# ESP32ProtypeBoard.net
KiCad netlist of a schematic drawn in EAGLE
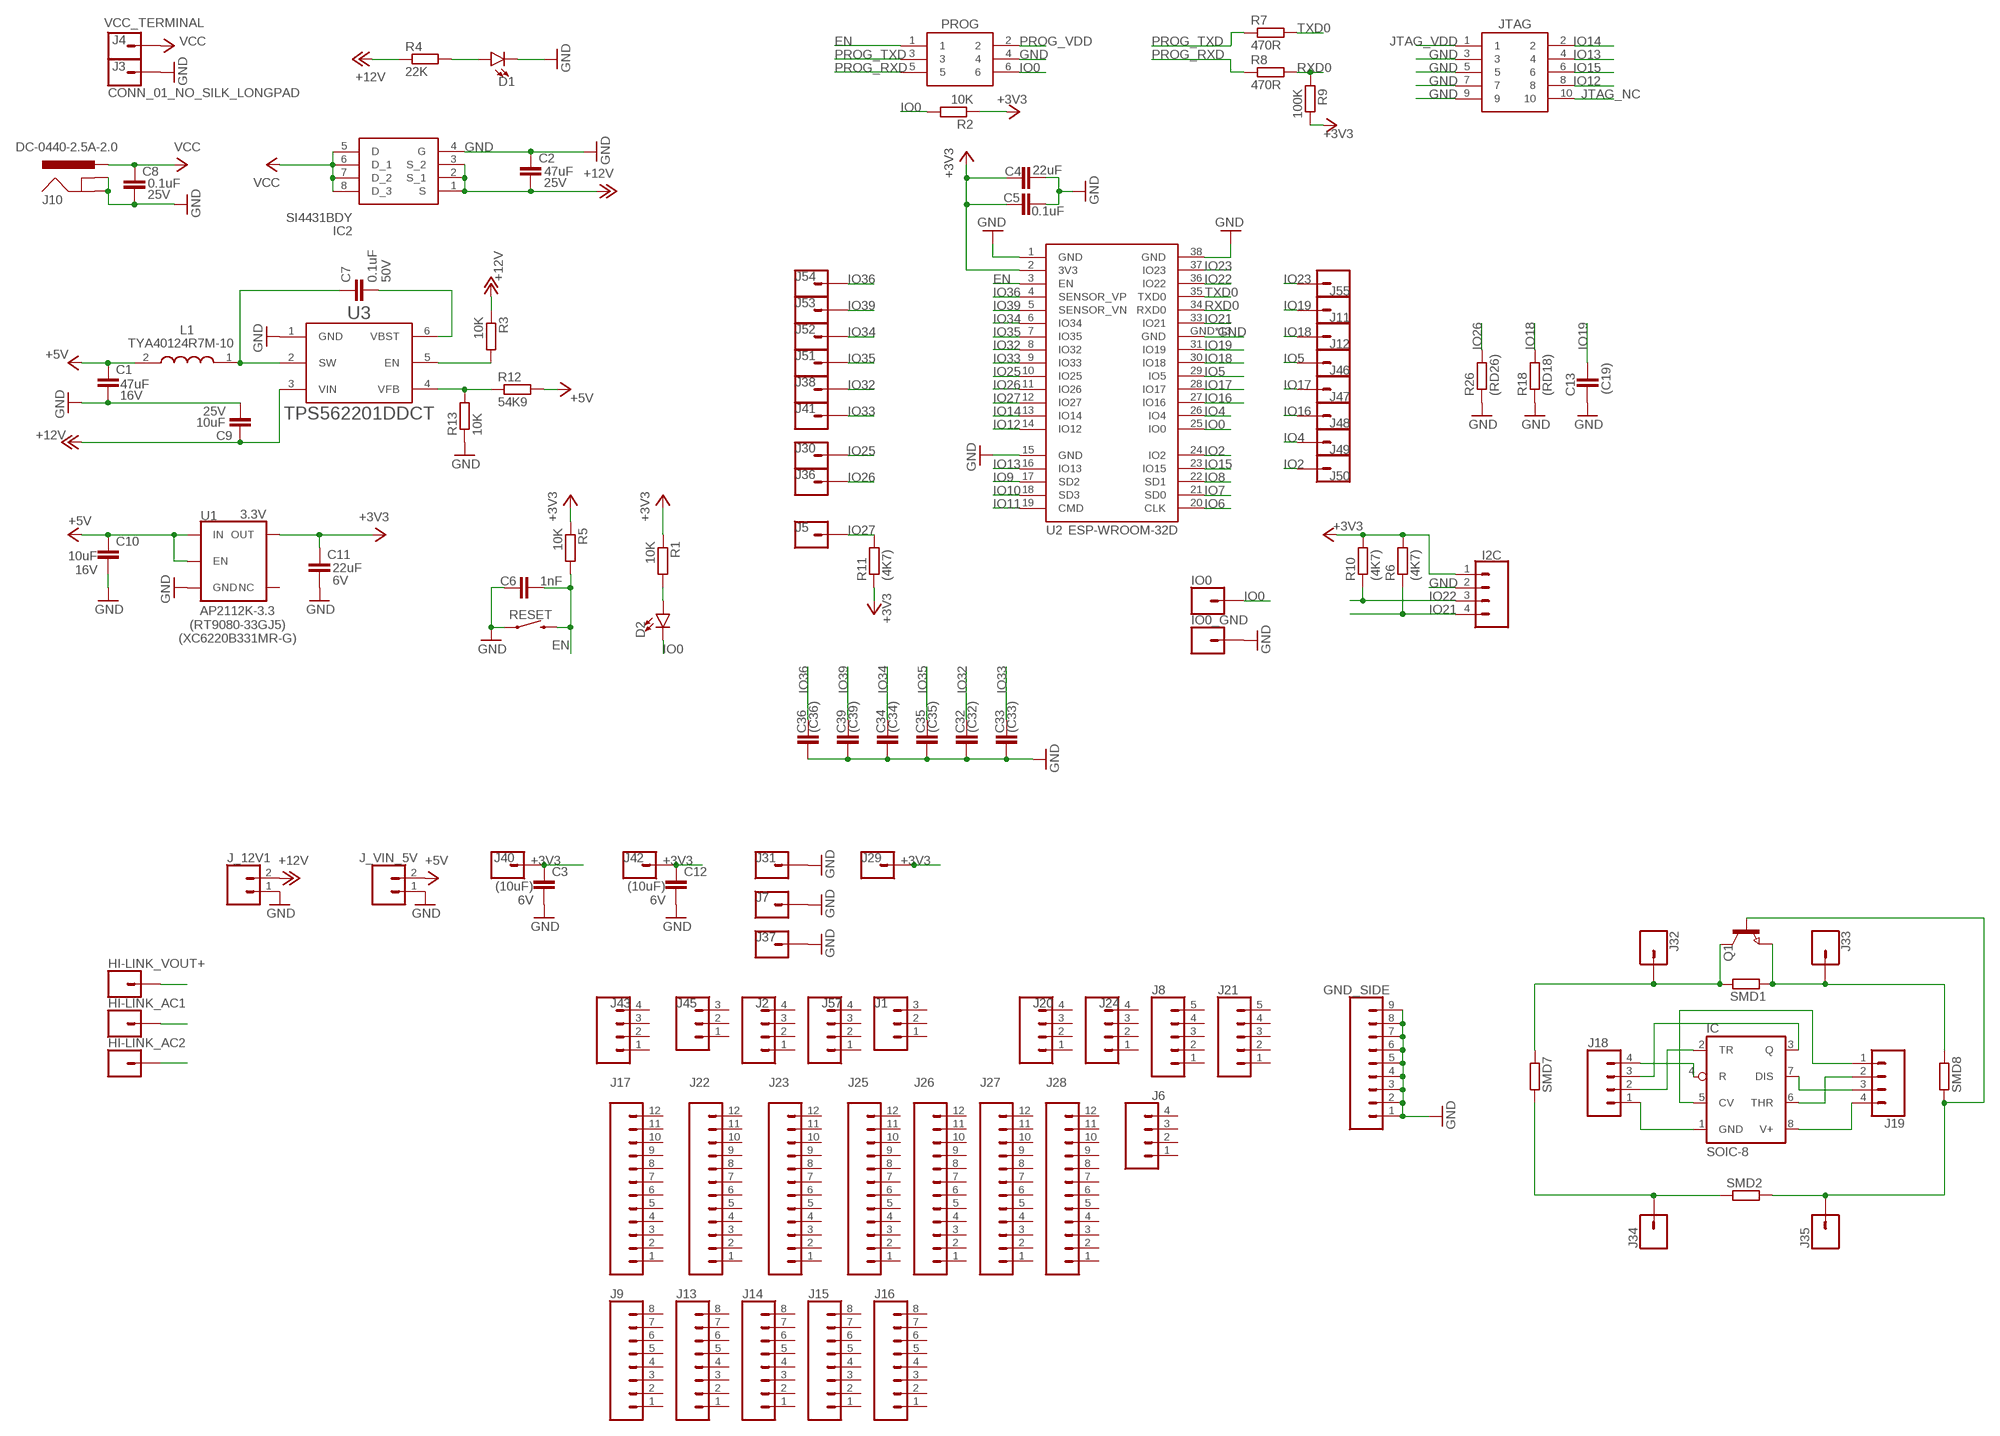
[diagram p0: schematic, sheet 1]

(export (version "E")
  (design (tool "Eeschema 10.0.6"))
  (components
    (comp (ref "C1")
      (value "47uF")
      (footprint "eagle-import:C1206K")
      (fields (field (name "VOLTAGE") "16V"))
      (libsource (lib "eagle-import") (part "C-EUC1206K"))
    )
    (comp (ref "C2")
      (value "47uF")
      (footprint "eagle-import:C1206K")
      (fields (field (name "VOLTAGE") "25V"))
      (libsource (lib "eagle-import") (part "C-EUC1206K"))
    )
    (comp (ref "C3")
      (value "(10uF)")
      (footprint "eagle-import:C0805K")
      (fields (field (name "VOLTAGE") "6V"))
      (libsource (lib "eagle-import") (part "C-EUC0805K"))
    )
    (comp (ref "C4")
      (value "22uF")
      (footprint "eagle-import:C0805K")
      (libsource (lib "eagle-import") (part "C-EUC0805K"))
    )
    (comp (ref "C5")
      (value "0.1uF")
      (footprint "eagle-import:C0805K")
      (libsource (lib "eagle-import") (part "C-EUC0805K"))
    )
    (comp (ref "C6")
      (value "1nF")
      (footprint "eagle-import:C0805K")
      (libsource (lib "eagle-import") (part "C-EUC0805K"))
    )
    (comp (ref "C7")
      (value "0.1uF")
      (footprint "eagle-import:C0805K")
      (fields (field (name "VOLTAGE") "50V"))
      (libsource (lib "eagle-import") (part "C-EUC0805K"))
    )
    (comp (ref "C8")
      (value "0.1uF")
      (footprint "eagle-import:C0805K")
      (fields (field (name "VOLTAGE") "25V"))
      (libsource (lib "eagle-import") (part "C-EUC0805K"))
    )
    (comp (ref "C9")
      (value "10uF")
      (footprint "eagle-import:C0805K")
      (fields (field (name "VOLTAGE") "25V"))
      (libsource (lib "eagle-import") (part "C-EUC0805K"))
    )
    (comp (ref "C10")
      (value "10uF")
      (footprint "eagle-import:C0805K")
      (fields (field (name "VOLTAGE") "16V"))
      (libsource (lib "eagle-import") (part "C-EUC0805K"))
    )
    (comp (ref "C11")
      (value "22uF")
      (footprint "eagle-import:C0805K")
      (fields (field (name "VOLTAGE") "6V"))
      (libsource (lib "eagle-import") (part "C-EUC0805K"))
    )
    (comp (ref "C12")
      (value "(10uF)")
      (footprint "eagle-import:C0805K")
      (fields (field (name "VOLTAGE") "6V"))
      (libsource (lib "eagle-import") (part "C-EUC0805K"))
    )
    (comp (ref "C13")
      (value "(C19)")
      (footprint "eagle-import:C0805K")
      (libsource (lib "eagle-import") (part "C-EUC0805K"))
    )
    (comp (ref "C32")
      (value "(C32)")
      (footprint "eagle-import:C0805K")
      (libsource (lib "eagle-import") (part "C-EUC0805K"))
    )
    (comp (ref "C33")
      (value "(C33)")
      (footprint "eagle-import:C0805K")
      (libsource (lib "eagle-import") (part "C-EUC0805K"))
    )
    (comp (ref "C34")
      (value "(C34)")
      (footprint "eagle-import:C0805K")
      (libsource (lib "eagle-import") (part "C-EUC0805K"))
    )
    (comp (ref "C35")
      (value "(C35)")
      (footprint "eagle-import:C0805K")
      (libsource (lib "eagle-import") (part "C-EUC0805K"))
    )
    (comp (ref "C36")
      (value "(C36)")
      (footprint "eagle-import:C0805K")
      (libsource (lib "eagle-import") (part "C-EUC0805K"))
    )
    (comp (ref "C39")
      (value "(C39)")
      (footprint "eagle-import:C0805K")
      (libsource (lib "eagle-import") (part "C-EUC0805K"))
    )
    (comp (ref "D1")
      (value "PWR")
      (footprint "eagle-import:CHIPLED_0805")
      (libsource (lib "eagle-import") (part "LEDCHIPLED_0805"))
    )
    (comp (ref "D2")
      (value "GREEN")
      (footprint "eagle-import:CHIPLED_0805")
      (libsource (lib "eagle-import") (part "LEDCHIPLED_0805"))
    )
    (comp (ref "GND_SIDE")
      (value "CONN_09NO_SILK")
      (footprint "eagle-import:1X09_NO_SILK")
      (libsource (lib "eagle-import") (part "CONN_09NO_SILK"))
    )
    (comp (ref "HI-LINK_AC1")
      (value "CONN_01PTH_NO_SILK_KIT")
      (footprint "eagle-import:1X01NS_KIT")
      (libsource (lib "eagle-import") (part "SparkFun-Connectors_513_CONN_01PTH_NO_SILK_KIT"))
    )
    (comp (ref "HI-LINK_AC2")
      (value "CONN_01PTH_NO_SILK_KIT")
      (footprint "eagle-import:1X01NS_KIT")
      (libsource (lib "eagle-import") (part "SparkFun-Connectors_513_CONN_01PTH_NO_SILK_KIT"))
    )
    (comp (ref "HI-LINK_VOUT+")
      (value "CONN_01PTH_NO_SILK_KIT")
      (footprint "eagle-import:1X01NS_KIT")
      (libsource (lib "eagle-import") (part "SparkFun-Connectors_513_CONN_01PTH_NO_SILK_KIT"))
    )
    (comp (ref "I2C")
      (value "CONN_041X04_NO_SILK")
      (footprint "eagle-import:1X04_NO_SILK")
      (libsource (lib "eagle-import") (part "SparkFun-Connectors_513_CONN_041X04_NO_SILK"))
    )
    (comp (ref "IC")
      (value "SOIC-8")
      (footprint "eagle-import:SO08")
      (libsource (lib "eagle-import") (part "555DLM"))
    )
    (comp (ref "IC2")
      (value "SI4431BDY")
      (footprint "eagle-import:SOIC127P600X175-8N")
      (fields (field (name "ARROW_PART_NUMBER") "SI4431BDY-T1-E3") (field (name "RS_PART_NUMBER") "7104714P"))
      (libsource (lib "eagle-import") (part "SI4431BDY-T1-E3"))
    )
    (comp (ref "IO0")
      (value "CONN_01PTH_NO_SILK_KIT")
      (footprint "eagle-import:1X01NS_KIT")
      (libsource (lib "eagle-import") (part "SparkFun-Connectors_513_CONN_01PTH_NO_SILK_KIT"))
    )
    (comp (ref "IO0_GND")
      (value "CONN_01PTH_NO_SILK_YES_STOP")
      (footprint "eagle-import:1X01_NO_SILK")
      (libsource (lib "eagle-import") (part "SparkFun-Connectors_513_CONN_01PTH_NO_SILK_YES_STOP"))
    )
    (comp (ref "J1")
      (value "CONN_03_NO_SILK")
      (footprint "eagle-import:1X03_NO_SILK")
      (libsource (lib "eagle-import") (part "CONN_03_NO_SILK"))
    )
    (comp (ref "J2")
      (value "CONN_04_NO_SILK")
      (footprint "eagle-import:1X04_NO_SILK")
      (libsource (lib "eagle-import") (part "CONN_04_NO_SILK"))
    )
    (comp (ref "J3")
      (value "CONN_01_NO_SILK_LONGPAD")
      (footprint "eagle-import:1X01_NO_SILK_LONGPAD")
      (libsource (lib "eagle-import") (part "CONN_01_NO_SILK_LONGPAD"))
    )
    (comp (ref "J4")
      (value "VCC_TERMINAL")
      (footprint "eagle-import:1X01_NO_SILK_LONGPAD")
      (libsource (lib "eagle-import") (part "CONN_01_NO_SILK_LONGPAD"))
    )
    (comp (ref "J5")
      (value "CONN_01_NO_SILK")
      (footprint "eagle-import:1X01_NO_SILK")
      (libsource (lib "eagle-import") (part "CONN_01_NO_SILK"))
    )
    (comp (ref "J6")
      (value "CONN_04_NO_SILK")
      (footprint "eagle-import:1X04_NO_SILK")
      (libsource (lib "eagle-import") (part "CONN_04_NO_SILK"))
    )
    (comp (ref "J7")
      (value "CONN_01_NO_SILK")
      (footprint "eagle-import:1X01_NO_SILK")
      (libsource (lib "eagle-import") (part "CONN_01_NO_SILK"))
    )
    (comp (ref "J8")
      (value "CONN_05_NO_SILK")
      (footprint "eagle-import:1X05_NO_SILK")
      (libsource (lib "eagle-import") (part "CONN_05_NO_SILK"))
    )
    (comp (ref "J9")
      (value "CONN_08NO_SILK_FEMALE_PTH")
      (footprint "eagle-import:1X08_NO_SILK")
      (libsource (lib "eagle-import") (part "CONN_08NO_SILK_FEMALE_PTH"))
    )
    (comp (ref "J10")
      (value "DC-0440-2.5A-2.0")
      (footprint "eagle-import:DC044025A20")
      (libsource (lib "eagle-import") (part "DC-0440-2.5A-2.0"))
    )
    (comp (ref "J11")
      (value "CONN_01PTH_NO_SILK_YES_STOP")
      (footprint "eagle-import:1X01_NO_SILK")
      (libsource (lib "eagle-import") (part "SparkFun-Connectors_513_CONN_01PTH_NO_SILK_YES_STOP"))
    )
    (comp (ref "J12")
      (value "CONN_01PTH_NO_SILK_YES_STOP")
      (footprint "eagle-import:1X01_NO_SILK")
      (libsource (lib "eagle-import") (part "SparkFun-Connectors_513_CONN_01PTH_NO_SILK_YES_STOP"))
    )
    (comp (ref "J13")
      (value "CONN_08NO_SILK_FEMALE_PTH")
      (footprint "eagle-import:1X08_NO_SILK")
      (libsource (lib "eagle-import") (part "CONN_08NO_SILK_FEMALE_PTH"))
    )
    (comp (ref "J14")
      (value "CONN_08NO_SILK_FEMALE_PTH")
      (footprint "eagle-import:1X08_NO_SILK")
      (libsource (lib "eagle-import") (part "CONN_08NO_SILK_FEMALE_PTH"))
    )
    (comp (ref "J15")
      (value "CONN_08NO_SILK_FEMALE_PTH")
      (footprint "eagle-import:1X08_NO_SILK")
      (libsource (lib "eagle-import") (part "CONN_08NO_SILK_FEMALE_PTH"))
    )
    (comp (ref "J16")
      (value "CONN_08NO_SILK_FEMALE_PTH")
      (footprint "eagle-import:1X08_NO_SILK")
      (libsource (lib "eagle-import") (part "CONN_08NO_SILK_FEMALE_PTH"))
    )
    (comp (ref "J17")
      (value "CONN_12NO_SILK")
      (footprint "eagle-import:1X12_NO_SILK")
      (libsource (lib "eagle-import") (part "CONN_12NO_SILK"))
    )
    (comp (ref "J18")
      (value "CONN_041X04_NO_SILK")
      (footprint "eagle-import:1X04_NO_SILK")
      (libsource (lib "eagle-import") (part "CONN_041X04_NO_SILK"))
    )
    (comp (ref "J19")
      (value "CONN_041X04_NO_SILK")
      (footprint "eagle-import:1X04_NO_SILK")
      (libsource (lib "eagle-import") (part "CONN_041X04_NO_SILK"))
    )
    (comp (ref "J20")
      (value "CONN_04_NO_SILK")
      (footprint "eagle-import:1X04_NO_SILK")
      (libsource (lib "eagle-import") (part "CONN_04_NO_SILK"))
    )
    (comp (ref "J21")
      (value "CONN_05_NO_SILK")
      (footprint "eagle-import:1X05_NO_SILK")
      (libsource (lib "eagle-import") (part "CONN_05_NO_SILK"))
    )
    (comp (ref "J22")
      (value "CONN_12NO_SILK")
      (footprint "eagle-import:1X12_NO_SILK")
      (libsource (lib "eagle-import") (part "CONN_12NO_SILK"))
    )
    (comp (ref "J23")
      (value "CONN_12NO_SILK")
      (footprint "eagle-import:1X12_NO_SILK")
      (libsource (lib "eagle-import") (part "CONN_12NO_SILK"))
    )
    (comp (ref "J24")
      (value "CONN_04_NO_SILK")
      (footprint "eagle-import:1X04_NO_SILK")
      (libsource (lib "eagle-import") (part "CONN_04_NO_SILK"))
    )
    (comp (ref "J25")
      (value "CONN_12NO_SILK")
      (footprint "eagle-import:1X12_NO_SILK")
      (libsource (lib "eagle-import") (part "CONN_12NO_SILK"))
    )
    (comp (ref "J26")
      (value "CONN_12NO_SILK")
      (footprint "eagle-import:1X12_NO_SILK")
      (libsource (lib "eagle-import") (part "CONN_12NO_SILK"))
    )
    (comp (ref "J27")
      (value "CONN_12NO_SILK")
      (footprint "eagle-import:1X12_NO_SILK")
      (libsource (lib "eagle-import") (part "CONN_12NO_SILK"))
    )
    (comp (ref "J28")
      (value "CONN_12NO_SILK")
      (footprint "eagle-import:1X12_NO_SILK")
      (libsource (lib "eagle-import") (part "CONN_12NO_SILK"))
    )
    (comp (ref "J29")
      (value "CONN_01_NO_SILK")
      (footprint "eagle-import:1X01_NO_SILK")
      (libsource (lib "eagle-import") (part "CONN_01_NO_SILK"))
    )
    (comp (ref "J30")
      (value "CONN_01_NO_SILK")
      (footprint "eagle-import:1X01_NO_SILK")
      (libsource (lib "eagle-import") (part "CONN_01_NO_SILK"))
    )
    (comp (ref "J31")
      (value "CONN_01_NO_SILK")
      (footprint "eagle-import:1X01_NO_SILK")
      (libsource (lib "eagle-import") (part "CONN_01_NO_SILK"))
    )
    (comp (ref "J32")
      (value "CONN_01PTH_NO_SILK_YES_STOP")
      (footprint "eagle-import:1X01_NO_SILK")
      (libsource (lib "eagle-import") (part "CONN_01PTH_NO_SILK_YES_STOP"))
    )
    (comp (ref "J33")
      (value "CONN_01PTH_NO_SILK_YES_STOP")
      (footprint "eagle-import:1X01_NO_SILK")
      (libsource (lib "eagle-import") (part "CONN_01PTH_NO_SILK_YES_STOP"))
    )
    (comp (ref "J34")
      (value "CONN_01PTH_NO_SILK_YES_STOP")
      (footprint "eagle-import:1X01_NO_SILK")
      (libsource (lib "eagle-import") (part "CONN_01PTH_NO_SILK_YES_STOP"))
    )
    (comp (ref "J35")
      (value "CONN_01PTH_NO_SILK_YES_STOP")
      (footprint "eagle-import:1X01_NO_SILK")
      (libsource (lib "eagle-import") (part "CONN_01PTH_NO_SILK_YES_STOP"))
    )
    (comp (ref "J36")
      (value "CONN_01_NO_SILK")
      (footprint "eagle-import:1X01_NO_SILK")
      (libsource (lib "eagle-import") (part "CONN_01_NO_SILK"))
    )
    (comp (ref "J37")
      (value "CONN_01_NO_SILK")
      (footprint "eagle-import:1X01_NO_SILK")
      (libsource (lib "eagle-import") (part "CONN_01_NO_SILK"))
    )
    (comp (ref "J38")
      (value "CONN_01_NO_SILK")
      (footprint "eagle-import:1X01_NO_SILK")
      (libsource (lib "eagle-import") (part "CONN_01_NO_SILK"))
    )
    (comp (ref "J40")
      (value "CONN_01_NO_SILK")
      (footprint "eagle-import:1X01_NO_SILK")
      (libsource (lib "eagle-import") (part "CONN_01_NO_SILK"))
    )
    (comp (ref "J41")
      (value "CONN_01_NO_SILK")
      (footprint "eagle-import:1X01_NO_SILK")
      (libsource (lib "eagle-import") (part "CONN_01_NO_SILK"))
    )
    (comp (ref "J42")
      (value "CONN_01_NO_SILK")
      (footprint "eagle-import:1X01_NO_SILK")
      (libsource (lib "eagle-import") (part "CONN_01_NO_SILK"))
    )
    (comp (ref "J43")
      (value "CONN_04_NO_SILK")
      (footprint "eagle-import:1X04_NO_SILK")
      (libsource (lib "eagle-import") (part "CONN_04_NO_SILK"))
    )
    (comp (ref "J45")
      (value "CONN_03_NO_SILK")
      (footprint "eagle-import:1X03_NO_SILK")
      (libsource (lib "eagle-import") (part "CONN_03_NO_SILK"))
    )
    (comp (ref "J46")
      (value "CONN_01PTH_NO_SILK_YES_STOP")
      (footprint "eagle-import:1X01_NO_SILK")
      (libsource (lib "eagle-import") (part "SparkFun-Connectors_513_CONN_01PTH_NO_SILK_YES_STOP"))
    )
    (comp (ref "J47")
      (value "CONN_01PTH_NO_SILK_YES_STOP")
      (footprint "eagle-import:1X01_NO_SILK")
      (libsource (lib "eagle-import") (part "SparkFun-Connectors_513_CONN_01PTH_NO_SILK_YES_STOP"))
    )
    (comp (ref "J48")
      (value "CONN_01PTH_NO_SILK_YES_STOP")
      (footprint "eagle-import:1X01_NO_SILK")
      (libsource (lib "eagle-import") (part "SparkFun-Connectors_513_CONN_01PTH_NO_SILK_YES_STOP"))
    )
    (comp (ref "J49")
      (value "CONN_01PTH_NO_SILK_YES_STOP")
      (footprint "eagle-import:1X01_NO_SILK")
      (libsource (lib "eagle-import") (part "SparkFun-Connectors_513_CONN_01PTH_NO_SILK_YES_STOP"))
    )
    (comp (ref "J50")
      (value "CONN_01PTH_NO_SILK_YES_STOP")
      (footprint "eagle-import:1X01_NO_SILK")
      (libsource (lib "eagle-import") (part "SparkFun-Connectors_513_CONN_01PTH_NO_SILK_YES_STOP"))
    )
    (comp (ref "J51")
      (value "CONN_01_NO_SILK")
      (footprint "eagle-import:1X01_NO_SILK")
      (libsource (lib "eagle-import") (part "CONN_01_NO_SILK"))
    )
    (comp (ref "J52")
      (value "CONN_01_NO_SILK")
      (footprint "eagle-import:1X01_NO_SILK")
      (libsource (lib "eagle-import") (part "CONN_01_NO_SILK"))
    )
    (comp (ref "J53")
      (value "CONN_01_NO_SILK")
      (footprint "eagle-import:1X01_NO_SILK")
      (libsource (lib "eagle-import") (part "CONN_01_NO_SILK"))
    )
    (comp (ref "J54")
      (value "CONN_01_NO_SILK")
      (footprint "eagle-import:1X01_NO_SILK")
      (libsource (lib "eagle-import") (part "CONN_01_NO_SILK"))
    )
    (comp (ref "J55")
      (value "CONN_01PTH_NO_SILK_YES_STOP")
      (footprint "eagle-import:1X01_NO_SILK")
      (libsource (lib "eagle-import") (part "SparkFun-Connectors_513_CONN_01PTH_NO_SILK_YES_STOP"))
    )
    (comp (ref "J57")
      (value "CONN_04_NO_SILK")
      (footprint "eagle-import:1X04_NO_SILK")
      (libsource (lib "eagle-import") (part "CONN_04_NO_SILK"))
    )
    (comp (ref "JTAG")
      (value "DC3-10-1P27")
      (footprint "eagle-import:DC3-10-1P27")
      (fields (field (name "ARROW_PART_NUMBER") "3220-10-0100-00"))
      (libsource (lib "eagle-import") (part "DC3-10-1P27"))
    )
    (comp (ref "J_12V1")
      (value "CONN_021X02_NO_SILK")
      (footprint "eagle-import:1X02_NO_SILK")
      (libsource (lib "eagle-import") (part "CONN_021X02_NO_SILK"))
    )
    (comp (ref "J_VIN_5V")
      (value "CONN_021X02_NO_SILK")
      (footprint "eagle-import:1X02_NO_SILK")
      (libsource (lib "eagle-import") (part "CONN_021X02_NO_SILK"))
    )
    (comp (ref "L1")
      (value "TYA40124R7M-10")
      (footprint "eagle-import:INDPM4040X130N")
      (libsource (lib "eagle-import") (part "TYA40124R7M-10"))
    )
    (comp (ref "PROG")
      (value "DC3-06-1P27")
      (footprint "eagle-import:DC3-06-1P27")
      (libsource (lib "eagle-import") (part "DC3-06-1P27"))
    )
    (comp (ref "Q1")
      (value "NPN-TRANSISTOR_SOT23")
      (footprint "eagle-import:SOT23")
      (libsource (lib "eagle-import") (part "NPN-TRANSISTOR_SOT23"))
    )
    (comp (ref "R1")
      (value "10K")
      (footprint "eagle-import:R0805")
      (libsource (lib "eagle-import") (part "R-EU_R0805"))
    )
    (comp (ref "R2")
      (value "10K")
      (footprint "eagle-import:R0805")
      (libsource (lib "eagle-import") (part "R-EU_R0805"))
    )
    (comp (ref "R3")
      (value "10K")
      (footprint "eagle-import:R0805")
      (libsource (lib "eagle-import") (part "R-EU_R0805"))
    )
    (comp (ref "R4")
      (value "22K")
      (footprint "eagle-import:R0805")
      (libsource (lib "eagle-import") (part "R-EU_R0805"))
    )
    (comp (ref "R5")
      (value "10K")
      (footprint "eagle-import:R0805")
      (libsource (lib "eagle-import") (part "R-EU_R0805"))
    )
    (comp (ref "R6")
      (value "(4K7)")
      (footprint "eagle-import:R0805")
      (libsource (lib "eagle-import") (part "R-EU_R0805"))
    )
    (comp (ref "R7")
      (value "470R")
      (footprint "eagle-import:R0805")
      (libsource (lib "eagle-import") (part "R-EU_R0805"))
    )
    (comp (ref "R8")
      (value "470R")
      (footprint "eagle-import:R0805")
      (libsource (lib "eagle-import") (part "R-EU_R0805"))
    )
    (comp (ref "R9")
      (value "100K")
      (footprint "eagle-import:R0805")
      (libsource (lib "eagle-import") (part "R-EU_R0805"))
    )
    (comp (ref "R10")
      (value "(4K7)")
      (footprint "eagle-import:R0805")
      (libsource (lib "eagle-import") (part "R-EU_R0805"))
    )
    (comp (ref "R11")
      (value "(4K7)")
      (footprint "eagle-import:R0805")
      (libsource (lib "eagle-import") (part "R-EU_R0805"))
    )
    (comp (ref "R12")
      (value "54K9")
      (footprint "eagle-import:R0805")
      (libsource (lib "eagle-import") (part "R-EU_R0805"))
    )
    (comp (ref "R13")
      (value "10K")
      (footprint "eagle-import:R0805")
      (libsource (lib "eagle-import") (part "R-EU_R0805"))
    )
    (comp (ref "R18")
      (value "(RD18)")
      (footprint "eagle-import:R0805")
      (libsource (lib "eagle-import") (part "R-EU_R0805"))
    )
    (comp (ref "R26")
      (value "(RD26)")
      (footprint "eagle-import:R0805")
      (libsource (lib "eagle-import") (part "R-EU_R0805"))
    )
    (comp (ref "RESET")
      (value "RESET")
      (footprint "eagle-import:TACTILE_SWITCH_SMD_4X3MM")
      (libsource (lib "eagle-import") (part "TACTILE_SWITCH_SMD_4X3MM"))
    )
    (comp (ref "SMD1")
      (value "RR1206")
      (footprint "eagle-import:R1206")
      (libsource (lib "eagle-import") (part "RR1206"))
    )
    (comp (ref "SMD2")
      (value "RR1206")
      (footprint "eagle-import:R1206")
      (libsource (lib "eagle-import") (part "RR1206"))
    )
    (comp (ref "SMD7")
      (value "RR1206")
      (footprint "eagle-import:R1206")
      (libsource (lib "eagle-import") (part "RR1206"))
    )
    (comp (ref "SMD8")
      (value "RR1206")
      (footprint "eagle-import:R1206")
      (libsource (lib "eagle-import") (part "RR1206"))
    )
    (comp (ref "U1")
      (value "3.3V")
      (footprint "eagle-import:SOT23-5")
      (libsource (lib "eagle-import") (part "V_REG_AP2112K-3.3V"))
    )
    (comp (ref "U2")
      (value "ESP-WROOM-32D")
      (footprint "eagle-import:ESP-WROOM-32D")
      (libsource (lib "eagle-import") (part "ESP-WROOM-32D"))
    )
    (comp (ref "U3")
      (value "TPS562201DDCTTEXAS_INSTRUMENTS_TPS562201DDCT_0_0")
      (footprint "eagle-import:TEXAS_INSTRUMENTS_TPS562201DDCT_0")
      (fields
        (field (name "DIGIKEY_PART_NUMBER") "296-43699-1-ND")
        (field (name "MF") "Texas Instruments")
        (field (name "MOUSER_PART_NUMBER") "595-TPS562201DDCT")
      )
      (libsource (lib "eagle-import") (part "TPS562201DDCTTEXAS_INSTRUMENTS_TPS562201DDCT_0_0"))
    )
  )
  (nets
    (net (code "1") (name "+3V3") (class "Default")
      (node (ref "C11") (pin "1") (pinfunction "1_1") (pintype "passive"))
      (node (ref "C12") (pin "1") (pinfunction "1_1") (pintype "passive"))
      (node (ref "C3") (pin "1") (pinfunction "1_1") (pintype "passive"))
      (node (ref "C4") (pin "1") (pinfunction "1_1") (pintype "passive"))
      (node (ref "C5") (pin "1") (pinfunction "1_1") (pintype "passive"))
      (node (ref "I2C") (pin "1") (pinfunction "1_1") (pintype "passive"))
      (node (ref "J29") (pin "1") (pinfunction "1_1") (pintype "passive"))
      (node (ref "J40") (pin "1") (pinfunction "1_1") (pintype "passive"))
      (node (ref "J42") (pin "1") (pinfunction "1_1") (pintype "passive"))
      (node (ref "R1") (pin "1") (pinfunction "1_1") (pintype "passive"))
      (node (ref "R10") (pin "2") (pinfunction "2_2") (pintype "passive"))
      (node (ref "R11") (pin "1") (pinfunction "1_1") (pintype "passive"))
      (node (ref "R2") (pin "1") (pinfunction "1_1") (pintype "passive"))
      (node (ref "R5") (pin "1") (pinfunction "1_1") (pintype "passive"))
      (node (ref "R6") (pin "2") (pinfunction "2_2") (pintype "passive"))
      (node (ref "R9") (pin "1") (pinfunction "1_1") (pintype "passive"))
      (node (ref "U1") (pin "5") (pinfunction "OUT_5") (pintype "passive"))
      (node (ref "U2") (pin "2") (pinfunction "3V3_2") (pintype "power_in"))
    )
    (net (code "2") (name "+5V") (class "Default")
      (node (ref "C1") (pin "1") (pinfunction "1_1") (pintype "passive"))
      (node (ref "C10") (pin "1") (pinfunction "1_1") (pintype "passive"))
      (node (ref "J_VIN_5V") (pin "2") (pinfunction "2_2") (pintype "passive"))
      (node (ref "L1") (pin "2") (pinfunction "2_2") (pintype "bidirectional"))
      (node (ref "R12") (pin "2") (pinfunction "2_2") (pintype "passive"))
      (node (ref "U1") (pin "1") (pinfunction "IN_1") (pintype "input"))
      (node (ref "U1") (pin "3") (pinfunction "EN_3") (pintype "input"))
    )
    (net (code "3") (name "+12V") (class "Default")
      (node (ref "C2") (pin "2") (pinfunction "2_2") (pintype "passive"))
      (node (ref "C9") (pin "1") (pinfunction "1_1") (pintype "passive"))
      (node (ref "IC2") (pin "1") (pinfunction "S_1") (pintype "bidirectional"))
      (node (ref "IC2") (pin "2") (pinfunction "S_1_2") (pintype "bidirectional"))
      (node (ref "IC2") (pin "3") (pinfunction "S_2_3") (pintype "bidirectional"))
      (node (ref "J_12V1") (pin "2") (pinfunction "2_2") (pintype "passive"))
      (node (ref "R3") (pin "1") (pinfunction "1_1") (pintype "passive"))
      (node (ref "R4") (pin "1") (pinfunction "1_1") (pintype "passive"))
      (node (ref "U3") (pin "3") (pinfunction "VIN_3") (pintype "power_in"))
    )
    (net (code "4") (name "/EN") (class "Default")
      (node (ref "C6") (pin "2") (pinfunction "2_2") (pintype "passive"))
      (node (ref "PROG") (pin "1") (pinfunction "1_1") (pintype "bidirectional"))
      (node (ref "R5") (pin "2") (pinfunction "2_2") (pintype "passive"))
      (node (ref "RESET") (pin "2") (pinfunction "2_2") (pintype "passive"))
      (node (ref "U2") (pin "3") (pinfunction "EN_3") (pintype "input"))
    )
    (net (code "5") (name "/IO0") (class "Default")
      (node (ref "D2") (pin "C") (pinfunction "C_C") (pintype "passive"))
      (node (ref "IO0") (pin "1") (pinfunction "1_1") (pintype "passive"))
      (node (ref "PROG") (pin "6") (pinfunction "6_6") (pintype "bidirectional"))
      (node (ref "R2") (pin "2") (pinfunction "2_2") (pintype "passive"))
      (node (ref "U2") (pin "25") (pinfunction "IO0_25") (pintype "bidirectional"))
    )
    (net (code "6") (name "/IO2") (class "Default")
      (node (ref "J50") (pin "1") (pinfunction "1_1") (pintype "passive"))
      (node (ref "U2") (pin "24") (pinfunction "IO2_24") (pintype "bidirectional"))
    )
    (net (code "7") (name "/IO4") (class "Default")
      (node (ref "J49") (pin "1") (pinfunction "1_1") (pintype "passive"))
      (node (ref "U2") (pin "26") (pinfunction "IO4_26") (pintype "bidirectional"))
    )
    (net (code "8") (name "/IO5") (class "Default")
      (node (ref "J46") (pin "1") (pinfunction "1_1") (pintype "passive"))
      (node (ref "U2") (pin "29") (pinfunction "IO5_29") (pintype "bidirectional"))
    )
    (net (code "9") (name "/IO6") (class "Default")
      (node (ref "U2") (pin "20") (pinfunction "CLK_20") (pintype "bidirectional"))
    )
    (net (code "10") (name "/IO7") (class "Default")
      (node (ref "U2") (pin "21") (pinfunction "SD0_21") (pintype "bidirectional"))
    )
    (net (code "11") (name "/IO8") (class "Default")
      (node (ref "U2") (pin "22") (pinfunction "SD1_22") (pintype "bidirectional"))
    )
    (net (code "12") (name "/IO9") (class "Default")
      (node (ref "U2") (pin "17") (pinfunction "SD2_17") (pintype "bidirectional"))
    )
    (net (code "13") (name "/IO10") (class "Default")
      (node (ref "U2") (pin "18") (pinfunction "SD3_18") (pintype "bidirectional"))
    )
    (net (code "14") (name "/IO11") (class "Default")
      (node (ref "U2") (pin "19") (pinfunction "CMD_19") (pintype "bidirectional"))
    )
    (net (code "15") (name "/IO12") (class "Default")
      (node (ref "JTAG") (pin "8") (pinfunction "8_8") (pintype "bidirectional"))
      (node (ref "U2") (pin "14") (pinfunction "IO12_14") (pintype "bidirectional"))
    )
    (net (code "16") (name "/IO13") (class "Default")
      (node (ref "JTAG") (pin "4") (pinfunction "4_4") (pintype "bidirectional"))
      (node (ref "U2") (pin "16") (pinfunction "IO13_16") (pintype "bidirectional"))
    )
    (net (code "17") (name "/IO14") (class "Default")
      (node (ref "JTAG") (pin "2") (pinfunction "2_2") (pintype "bidirectional"))
      (node (ref "U2") (pin "13") (pinfunction "IO14_13") (pintype "bidirectional"))
    )
    (net (code "18") (name "/IO15") (class "Default")
      (node (ref "JTAG") (pin "6") (pinfunction "6_6") (pintype "bidirectional"))
      (node (ref "U2") (pin "23") (pinfunction "IO15_23") (pintype "bidirectional"))
    )
    (net (code "19") (name "/IO16") (class "Default")
      (node (ref "J48") (pin "1") (pinfunction "1_1") (pintype "passive"))
      (node (ref "U2") (pin "27") (pinfunction "IO16_27") (pintype "bidirectional"))
    )
    (net (code "20") (name "/IO17") (class "Default")
      (node (ref "J47") (pin "1") (pinfunction "1_1") (pintype "passive"))
      (node (ref "U2") (pin "28") (pinfunction "IO17_28") (pintype "bidirectional"))
    )
    (net (code "21") (name "/IO18") (class "Default")
      (node (ref "J12") (pin "1") (pinfunction "1_1") (pintype "passive"))
      (node (ref "R18") (pin "2") (pinfunction "2_2") (pintype "passive"))
      (node (ref "U2") (pin "30") (pinfunction "IO18_30") (pintype "bidirectional"))
    )
    (net (code "22") (name "/IO19") (class "Default")
      (node (ref "C13") (pin "1") (pinfunction "1_1") (pintype "passive"))
      (node (ref "J11") (pin "1") (pinfunction "1_1") (pintype "passive"))
      (node (ref "U2") (pin "31") (pinfunction "IO19_31") (pintype "bidirectional"))
    )
    (net (code "23") (name "/IO21") (class "Default")
      (node (ref "I2C") (pin "4") (pinfunction "4_4") (pintype "passive"))
      (node (ref "R6") (pin "1") (pinfunction "1_1") (pintype "passive"))
      (node (ref "U2") (pin "33") (pinfunction "IO21_33") (pintype "bidirectional"))
    )
    (net (code "24") (name "/IO22") (class "Default")
      (node (ref "I2C") (pin "3") (pinfunction "3_3") (pintype "passive"))
      (node (ref "R10") (pin "1") (pinfunction "1_1") (pintype "passive"))
      (node (ref "U2") (pin "36") (pinfunction "IO22_36") (pintype "bidirectional"))
    )
    (net (code "25") (name "/IO23") (class "Default")
      (node (ref "J55") (pin "1") (pinfunction "1_1") (pintype "passive"))
      (node (ref "U2") (pin "37") (pinfunction "IO23_37") (pintype "bidirectional"))
    )
    (net (code "26") (name "/IO25") (class "Default")
      (node (ref "J30") (pin "1") (pinfunction "1_1") (pintype "passive"))
      (node (ref "U2") (pin "10") (pinfunction "IO25_10") (pintype "bidirectional"))
    )
    (net (code "27") (name "/IO26") (class "Default")
      (node (ref "J36") (pin "1") (pinfunction "1_1") (pintype "passive"))
      (node (ref "R26") (pin "2") (pinfunction "2_2") (pintype "passive"))
      (node (ref "U2") (pin "11") (pinfunction "IO26_11") (pintype "bidirectional"))
    )
    (net (code "28") (name "/IO27") (class "Default")
      (node (ref "J5") (pin "1") (pinfunction "1_1") (pintype "passive"))
      (node (ref "R11") (pin "2") (pinfunction "2_2") (pintype "passive"))
      (node (ref "U2") (pin "12") (pinfunction "IO27_12") (pintype "bidirectional"))
    )
    (net (code "29") (name "/IO32") (class "Default")
      (node (ref "C32") (pin "2") (pinfunction "2_2") (pintype "passive"))
      (node (ref "J38") (pin "1") (pinfunction "1_1") (pintype "passive"))
      (node (ref "U2") (pin "8") (pinfunction "IO32_8") (pintype "bidirectional"))
    )
    (net (code "30") (name "/IO33") (class "Default")
      (node (ref "C33") (pin "2") (pinfunction "2_2") (pintype "passive"))
      (node (ref "J41") (pin "1") (pinfunction "1_1") (pintype "passive"))
      (node (ref "U2") (pin "9") (pinfunction "IO33_9") (pintype "bidirectional"))
    )
    (net (code "31") (name "/IO34") (class "Default")
      (node (ref "C34") (pin "2") (pinfunction "2_2") (pintype "passive"))
      (node (ref "J52") (pin "1") (pinfunction "1_1") (pintype "passive"))
      (node (ref "U2") (pin "6") (pinfunction "IO34_6") (pintype "bidirectional"))
    )
    (net (code "32") (name "/IO35") (class "Default")
      (node (ref "C35") (pin "2") (pinfunction "2_2") (pintype "passive"))
      (node (ref "J51") (pin "1") (pinfunction "1_1") (pintype "passive"))
      (node (ref "U2") (pin "7") (pinfunction "IO35_7") (pintype "bidirectional"))
    )
    (net (code "33") (name "/IO36") (class "Default")
      (node (ref "C36") (pin "2") (pinfunction "2_2") (pintype "passive"))
      (node (ref "J54") (pin "1") (pinfunction "1_1") (pintype "passive"))
      (node (ref "U2") (pin "4") (pinfunction "SENSOR_VP_4") (pintype "bidirectional"))
    )
    (net (code "34") (name "/IO39") (class "Default")
      (node (ref "C39") (pin "2") (pinfunction "2_2") (pintype "passive"))
      (node (ref "J53") (pin "1") (pinfunction "1_1") (pintype "passive"))
      (node (ref "U2") (pin "5") (pinfunction "SENSOR_VN_5") (pintype "bidirectional"))
    )
    (net (code "35") (name "/JTAG_NC") (class "Default")
      (node (ref "JTAG") (pin "10") (pinfunction "10_10") (pintype "bidirectional"))
    )
    (net (code "36") (name "/JTAG_VDD") (class "Default")
      (node (ref "JTAG") (pin "1") (pinfunction "1_1") (pintype "bidirectional"))
    )
    (net (code "37") (name "/PROG_RXD") (class "Default")
      (node (ref "PROG") (pin "5") (pinfunction "5_5") (pintype "bidirectional"))
      (node (ref "R8") (pin "1") (pinfunction "1_1") (pintype "passive"))
    )
    (net (code "38") (name "/PROG_TXD") (class "Default")
      (node (ref "PROG") (pin "3") (pinfunction "3_3") (pintype "bidirectional"))
      (node (ref "R7") (pin "1") (pinfunction "1_1") (pintype "passive"))
    )
    (net (code "39") (name "/PROG_VDD") (class "Default")
      (node (ref "PROG") (pin "2") (pinfunction "2_2") (pintype "bidirectional"))
    )
    (net (code "40") (name "/RXD0") (class "Default")
      (node (ref "R8") (pin "2") (pinfunction "2_2") (pintype "passive"))
      (node (ref "R9") (pin "2") (pinfunction "2_2") (pintype "passive"))
      (node (ref "U2") (pin "34") (pinfunction "RXD0_34") (pintype "bidirectional"))
    )
    (net (code "41") (name "/TXD0") (class "Default")
      (node (ref "R7") (pin "2") (pinfunction "2_2") (pintype "passive"))
      (node (ref "U2") (pin "35") (pinfunction "TXD0_35") (pintype "bidirectional"))
    )
    (net (code "42") (name "GND") (class "Default")
      (node (ref "C1") (pin "2") (pinfunction "2_2") (pintype "passive"))
      (node (ref "C10") (pin "2") (pinfunction "2_2") (pintype "passive"))
      (node (ref "C11") (pin "2") (pinfunction "2_2") (pintype "passive"))
      (node (ref "C12") (pin "2") (pinfunction "2_2") (pintype "passive"))
      (node (ref "C13") (pin "2") (pinfunction "2_2") (pintype "passive"))
      (node (ref "C2") (pin "1") (pinfunction "1_1") (pintype "passive"))
      (node (ref "C3") (pin "2") (pinfunction "2_2") (pintype "passive"))
      (node (ref "C32") (pin "1") (pinfunction "1_1") (pintype "passive"))
      (node (ref "C33") (pin "1") (pinfunction "1_1") (pintype "passive"))
      (node (ref "C34") (pin "1") (pinfunction "1_1") (pintype "passive"))
      (node (ref "C35") (pin "1") (pinfunction "1_1") (pintype "passive"))
      (node (ref "C36") (pin "1") (pinfunction "1_1") (pintype "passive"))
      (node (ref "C39") (pin "1") (pinfunction "1_1") (pintype "passive"))
      (node (ref "C4") (pin "2") (pinfunction "2_2") (pintype "passive"))
      (node (ref "C5") (pin "2") (pinfunction "2_2") (pintype "passive"))
      (node (ref "C6") (pin "1") (pinfunction "1_1") (pintype "passive"))
      (node (ref "C8") (pin "2") (pinfunction "2_2") (pintype "passive"))
      (node (ref "C9") (pin "2") (pinfunction "2_2") (pintype "passive"))
      (node (ref "D1") (pin "C") (pinfunction "C_C") (pintype "passive"))
      (node (ref "GND_SIDE") (pin "1") (pinfunction "1_1") (pintype "passive"))
      (node (ref "GND_SIDE") (pin "2") (pinfunction "2_2") (pintype "passive"))
      (node (ref "GND_SIDE") (pin "3") (pinfunction "3_3") (pintype "passive"))
      (node (ref "GND_SIDE") (pin "4") (pinfunction "4_4") (pintype "passive"))
      (node (ref "GND_SIDE") (pin "5") (pinfunction "5_5") (pintype "passive"))
      (node (ref "GND_SIDE") (pin "6") (pinfunction "6_6") (pintype "passive"))
      (node (ref "GND_SIDE") (pin "7") (pinfunction "7_7") (pintype "passive"))
      (node (ref "GND_SIDE") (pin "8") (pinfunction "8_8") (pintype "passive"))
      (node (ref "GND_SIDE") (pin "9") (pinfunction "9_9") (pintype "passive"))
      (node (ref "I2C") (pin "2") (pinfunction "2_2") (pintype "passive"))
      (node (ref "IC2") (pin "4") (pinfunction "G_4") (pintype "bidirectional"))
      (node (ref "IO0_GND") (pin "1") (pinfunction "1_1") (pintype "passive"))
      (node (ref "J10") (pin "2") (pinfunction "GND_2") (pintype "bidirectional"))
      (node (ref "J10") (pin "3") (pinfunction "GNDBREAK_3") (pintype "bidirectional"))
      (node (ref "J3") (pin "1") (pinfunction "1_1") (pintype "passive"))
      (node (ref "J31") (pin "1") (pinfunction "1_1") (pintype "passive"))
      (node (ref "J37") (pin "1") (pinfunction "1_1") (pintype "passive"))
      (node (ref "J7") (pin "1") (pinfunction "1_1") (pintype "passive"))
      (node (ref "JTAG") (pin "3") (pinfunction "3_3") (pintype "bidirectional"))
      (node (ref "JTAG") (pin "5") (pinfunction "5_5") (pintype "bidirectional"))
      (node (ref "JTAG") (pin "7") (pinfunction "7_7") (pintype "bidirectional"))
      (node (ref "JTAG") (pin "9") (pinfunction "9_9") (pintype "bidirectional"))
      (node (ref "J_12V1") (pin "1") (pinfunction "1_1") (pintype "passive"))
      (node (ref "J_VIN_5V") (pin "1") (pinfunction "1_1") (pintype "passive"))
      (node (ref "PROG") (pin "4") (pinfunction "4_4") (pintype "bidirectional"))
      (node (ref "R13") (pin "1") (pinfunction "1_1") (pintype "passive"))
      (node (ref "R18") (pin "1") (pinfunction "1_1") (pintype "passive"))
      (node (ref "R26") (pin "1") (pinfunction "1_1") (pintype "passive"))
      (node (ref "RESET") (pin "1") (pinfunction "1_1") (pintype "passive"))
      (node (ref "U1") (pin "2") (pinfunction "GND_2") (pintype "input"))
      (node (ref "U2") (pin "1") (pinfunction "GND_1") (pintype "power_in"))
      (node (ref "U2") (pin "15") (pinfunction "GND_15") (pintype "power_in"))
      (node (ref "U2") (pin "38") (pinfunction "GND_38") (pintype "power_in"))
      (node (ref "U2") (pin "GND") (pinfunction "GND_GND") (pintype "power_in"))
      (node (ref "U2") (pin "GND_1") (pinfunction "GND_GND_1") (pintype "power_in"))
      (node (ref "U2") (pin "GND_10") (pinfunction "GND_GND_10") (pintype "power_in"))
      (node (ref "U2") (pin "GND_11") (pinfunction "GND_GND_11") (pintype "power_in"))
      (node (ref "U2") (pin "GND_12") (pinfunction "GND_GND_12") (pintype "power_in"))
      (node (ref "U2") (pin "GND_2") (pinfunction "GND_GND_2") (pintype "power_in"))
      (node (ref "U2") (pin "GND_3") (pinfunction "GND_GND_3") (pintype "power_in"))
      (node (ref "U2") (pin "GND_4") (pinfunction "GND_GND_4") (pintype "power_in"))
      (node (ref "U2") (pin "GND_5") (pinfunction "GND_GND_5") (pintype "power_in"))
      (node (ref "U2") (pin "GND_6") (pinfunction "GND_GND_6") (pintype "power_in"))
      (node (ref "U2") (pin "GND_7") (pinfunction "GND_GND_7") (pintype "power_in"))
      (node (ref "U2") (pin "GND_8") (pinfunction "GND_GND_8") (pintype "power_in"))
      (node (ref "U2") (pin "GND_9") (pinfunction "GND_GND_9") (pintype "power_in"))
      (node (ref "U3") (pin "1") (pinfunction "GND_1") (pintype "power_in"))
    )
    (net (code "43") (name "Net-(D1-PadA)") (class "Default")
      (node (ref "D1") (pin "A") (pinfunction "A_A") (pintype "passive"))
      (node (ref "R4") (pin "2") (pinfunction "2_2") (pintype "passive"))
    )
    (net (code "44") (name "Net-(D2-PadA)") (class "Default")
      (node (ref "D2") (pin "A") (pinfunction "A_A") (pintype "passive"))
      (node (ref "R1") (pin "2") (pinfunction "2_2") (pintype "passive"))
    )
    (net (code "45") (name "Net-(IC-CV)") (class "Default")
      (node (ref "IC") (pin "5") (pinfunction "CV_5") (pintype "input"))
      (node (ref "J19") (pin "1") (pinfunction "1_1") (pintype "passive"))
    )
    (net (code "46") (name "Net-(IC-DIS)") (class "Default")
      (node (ref "IC") (pin "7") (pinfunction "DIS_7") (pintype "input"))
      (node (ref "J19") (pin "3") (pinfunction "3_3") (pintype "passive"))
    )
    (net (code "47") (name "Net-(IC-GND)") (class "Default")
      (node (ref "IC") (pin "1") (pinfunction "GND_1") (pintype "power_in"))
      (node (ref "J18") (pin "1") (pinfunction "1_1") (pintype "passive"))
    )
    (net (code "48") (name "Net-(IC-Q)") (class "Default")
      (node (ref "IC") (pin "3") (pinfunction "Q_3") (pintype "output"))
      (node (ref "J18") (pin "3") (pinfunction "3_3") (pintype "passive"))
    )
    (net (code "49") (name "Net-(IC-R)") (class "Default")
      (node (ref "IC") (pin "4") (pinfunction "R_4") (pintype "input"))
      (node (ref "J18") (pin "4") (pinfunction "4_4") (pintype "passive"))
    )
    (net (code "50") (name "Net-(IC-THR)") (class "Default")
      (node (ref "IC") (pin "6") (pinfunction "THR_6") (pintype "input"))
      (node (ref "J19") (pin "2") (pinfunction "2_2") (pintype "passive"))
    )
    (net (code "51") (name "Net-(IC-TR)") (class "Default")
      (node (ref "IC") (pin "2") (pinfunction "TR_2") (pintype "input"))
      (node (ref "J18") (pin "2") (pinfunction "2_2") (pintype "passive"))
    )
    (net (code "52") (name "Net-(IC-V+)") (class "Default")
      (node (ref "IC") (pin "8") (pinfunction "V+_8") (pintype "power_in"))
      (node (ref "J19") (pin "4") (pinfunction "4_4") (pintype "passive"))
    )
    (net (code "53") (name "Net-(J34-Pad1)") (class "Default")
      (node (ref "J34") (pin "1") (pinfunction "1_1") (pintype "passive"))
      (node (ref "SMD2") (pin "1") (pinfunction "1_1") (pintype "passive"))
      (node (ref "SMD7") (pin "2") (pinfunction "2_2") (pintype "passive"))
    )
    (net (code "54") (name "Net-(Q1-B)") (class "Default")
      (node (ref "J35") (pin "1") (pinfunction "1_1") (pintype "passive"))
      (node (ref "Q1") (pin "1") (pinfunction "B_1") (pintype "passive"))
      (node (ref "SMD2") (pin "2") (pinfunction "2_2") (pintype "passive"))
      (node (ref "SMD8") (pin "2") (pinfunction "2_2") (pintype "passive"))
    )
    (net (code "55") (name "Net-(Q1-C)") (class "Default")
      (node (ref "J32") (pin "1") (pinfunction "1_1") (pintype "passive"))
      (node (ref "Q1") (pin "3") (pinfunction "C_3") (pintype "passive"))
      (node (ref "SMD1") (pin "2") (pinfunction "2_2") (pintype "passive"))
      (node (ref "SMD7") (pin "1") (pinfunction "1_1") (pintype "passive"))
    )
    (net (code "56") (name "Net-(Q1-E)") (class "Default")
      (node (ref "J33") (pin "1") (pinfunction "1_1") (pintype "passive"))
      (node (ref "Q1") (pin "2") (pinfunction "E_2") (pintype "passive"))
      (node (ref "SMD1") (pin "1") (pinfunction "1_1") (pintype "passive"))
      (node (ref "SMD8") (pin "1") (pinfunction "1_1") (pintype "passive"))
    )
    (net (code "57") (name "Net-(U3-EN)") (class "Default")
      (node (ref "R3") (pin "2") (pinfunction "2_2") (pintype "passive"))
      (node (ref "U3") (pin "5") (pinfunction "EN_5") (pintype "input"))
    )
    (net (code "58") (name "Net-(U3-SW)") (class "Default")
      (node (ref "C7") (pin "1") (pinfunction "1_1") (pintype "passive"))
      (node (ref "L1") (pin "1") (pinfunction "1_1") (pintype "bidirectional"))
      (node (ref "U3") (pin "2") (pinfunction "SW_2") (pintype "passive"))
    )
    (net (code "59") (name "Net-(U3-VBST)") (class "Default")
      (node (ref "C7") (pin "2") (pinfunction "2_2") (pintype "passive"))
      (node (ref "U3") (pin "6") (pinfunction "VBST_6") (pintype "power_in"))
    )
    (net (code "60") (name "Net-(U3-VFB)") (class "Default")
      (node (ref "R12") (pin "1") (pinfunction "1_1") (pintype "passive"))
      (node (ref "R13") (pin "2") (pinfunction "2_2") (pintype "passive"))
      (node (ref "U3") (pin "4") (pinfunction "VFB_4") (pintype "passive"))
    )
    (net (code "61") (name "VCC") (class "Default")
      (node (ref "C8") (pin "1") (pinfunction "1_1") (pintype "passive"))
      (node (ref "IC2") (pin "5") (pinfunction "D_5") (pintype "bidirectional"))
      (node (ref "IC2") (pin "6") (pinfunction "D_1_6") (pintype "bidirectional"))
      (node (ref "IC2") (pin "7") (pinfunction "D_2_7") (pintype "bidirectional"))
      (node (ref "IC2") (pin "8") (pinfunction "D_3_8") (pintype "bidirectional"))
      (node (ref "J10") (pin "1") (pinfunction "PWR_1") (pintype "bidirectional"))
      (node (ref "J4") (pin "1") (pinfunction "1_1") (pintype "passive"))
    )
    (net (code "62") (name "unconnected-(HI-LINK_AC1-Pad1)") (class "Default")
      (node (ref "HI-LINK_AC1") (pin "1") (pinfunction "1_1") (pintype "passive"))
    )
    (net (code "63") (name "unconnected-(HI-LINK_AC2-Pad1)") (class "Default")
      (node (ref "HI-LINK_AC2") (pin "1") (pinfunction "1_1") (pintype "passive"))
    )
    (net (code "64") (name "unconnected-(HI-LINK_VOUT+-Pad1)") (class "Default")
      (node (ref "HI-LINK_VOUT+") (pin "1") (pinfunction "1_1") (pintype "passive"))
    )
    (net (code "65") (name "unconnected-(J1-Pad1)") (class "Default")
      (node (ref "J1") (pin "1") (pinfunction "1_1") (pintype "passive"))
    )
    (net (code "66") (name "unconnected-(J1-Pad2)") (class "Default")
      (node (ref "J1") (pin "2") (pinfunction "2_2") (pintype "passive"))
    )
    (net (code "67") (name "unconnected-(J1-Pad3)") (class "Default")
      (node (ref "J1") (pin "3") (pinfunction "3_3") (pintype "passive"))
    )
    (net (code "68") (name "unconnected-(J2-Pad1)") (class "Default")
      (node (ref "J2") (pin "1") (pinfunction "1_1") (pintype "passive"))
    )
    (net (code "69") (name "unconnected-(J2-Pad2)") (class "Default")
      (node (ref "J2") (pin "2") (pinfunction "2_2") (pintype "passive"))
    )
    (net (code "70") (name "unconnected-(J2-Pad3)") (class "Default")
      (node (ref "J2") (pin "3") (pinfunction "3_3") (pintype "passive"))
    )
    (net (code "71") (name "unconnected-(J2-Pad4)") (class "Default")
      (node (ref "J2") (pin "4") (pinfunction "4_4") (pintype "passive"))
    )
    (net (code "72") (name "unconnected-(J6-Pad1)") (class "Default")
      (node (ref "J6") (pin "1") (pinfunction "1_1") (pintype "passive"))
    )
    (net (code "73") (name "unconnected-(J6-Pad2)") (class "Default")
      (node (ref "J6") (pin "2") (pinfunction "2_2") (pintype "passive"))
    )
    (net (code "74") (name "unconnected-(J6-Pad3)") (class "Default")
      (node (ref "J6") (pin "3") (pinfunction "3_3") (pintype "passive"))
    )
    (net (code "75") (name "unconnected-(J6-Pad4)") (class "Default")
      (node (ref "J6") (pin "4") (pinfunction "4_4") (pintype "passive"))
    )
    (net (code "76") (name "unconnected-(J8-Pad1)") (class "Default")
      (node (ref "J8") (pin "1") (pinfunction "1_1") (pintype "passive"))
    )
    (net (code "77") (name "unconnected-(J8-Pad2)") (class "Default")
      (node (ref "J8") (pin "2") (pinfunction "2_2") (pintype "passive"))
    )
    (net (code "78") (name "unconnected-(J8-Pad3)") (class "Default")
      (node (ref "J8") (pin "3") (pinfunction "3_3") (pintype "passive"))
    )
    (net (code "79") (name "unconnected-(J8-Pad4)") (class "Default")
      (node (ref "J8") (pin "4") (pinfunction "4_4") (pintype "passive"))
    )
    (net (code "80") (name "unconnected-(J8-Pad5)") (class "Default")
      (node (ref "J8") (pin "5") (pinfunction "5_5") (pintype "passive"))
    )
    (net (code "81") (name "unconnected-(J9-Pad1)") (class "Default")
      (node (ref "J9") (pin "1") (pinfunction "1_1") (pintype "passive"))
    )
    (net (code "82") (name "unconnected-(J9-Pad2)") (class "Default")
      (node (ref "J9") (pin "2") (pinfunction "2_2") (pintype "passive"))
    )
    (net (code "83") (name "unconnected-(J9-Pad3)") (class "Default")
      (node (ref "J9") (pin "3") (pinfunction "3_3") (pintype "passive"))
    )
    (net (code "84") (name "unconnected-(J9-Pad4)") (class "Default")
      (node (ref "J9") (pin "4") (pinfunction "4_4") (pintype "passive"))
    )
    (net (code "85") (name "unconnected-(J9-Pad5)") (class "Default")
      (node (ref "J9") (pin "5") (pinfunction "5_5") (pintype "passive"))
    )
    (net (code "86") (name "unconnected-(J9-Pad6)") (class "Default")
      (node (ref "J9") (pin "6") (pinfunction "6_6") (pintype "passive"))
    )
    (net (code "87") (name "unconnected-(J9-Pad7)") (class "Default")
      (node (ref "J9") (pin "7") (pinfunction "7_7") (pintype "passive"))
    )
    (net (code "88") (name "unconnected-(J9-Pad8)") (class "Default")
      (node (ref "J9") (pin "8") (pinfunction "8_8") (pintype "passive"))
    )
    (net (code "89") (name "unconnected-(J13-Pad1)") (class "Default")
      (node (ref "J13") (pin "1") (pinfunction "1_1") (pintype "passive"))
    )
    (net (code "90") (name "unconnected-(J13-Pad2)") (class "Default")
      (node (ref "J13") (pin "2") (pinfunction "2_2") (pintype "passive"))
    )
    (net (code "91") (name "unconnected-(J13-Pad3)") (class "Default")
      (node (ref "J13") (pin "3") (pinfunction "3_3") (pintype "passive"))
    )
    (net (code "92") (name "unconnected-(J13-Pad4)") (class "Default")
      (node (ref "J13") (pin "4") (pinfunction "4_4") (pintype "passive"))
    )
    (net (code "93") (name "unconnected-(J13-Pad5)") (class "Default")
      (node (ref "J13") (pin "5") (pinfunction "5_5") (pintype "passive"))
    )
    (net (code "94") (name "unconnected-(J13-Pad6)") (class "Default")
      (node (ref "J13") (pin "6") (pinfunction "6_6") (pintype "passive"))
    )
    (net (code "95") (name "unconnected-(J13-Pad7)") (class "Default")
      (node (ref "J13") (pin "7") (pinfunction "7_7") (pintype "passive"))
    )
    (net (code "96") (name "unconnected-(J13-Pad8)") (class "Default")
      (node (ref "J13") (pin "8") (pinfunction "8_8") (pintype "passive"))
    )
    (net (code "97") (name "unconnected-(J14-Pad1)") (class "Default")
      (node (ref "J14") (pin "1") (pinfunction "1_1") (pintype "passive"))
    )
    (net (code "98") (name "unconnected-(J14-Pad2)") (class "Default")
      (node (ref "J14") (pin "2") (pinfunction "2_2") (pintype "passive"))
    )
    (net (code "99") (name "unconnected-(J14-Pad3)") (class "Default")
      (node (ref "J14") (pin "3") (pinfunction "3_3") (pintype "passive"))
    )
    (net (code "100") (name "unconnected-(J14-Pad4)") (class "Default")
      (node (ref "J14") (pin "4") (pinfunction "4_4") (pintype "passive"))
    )
    (net (code "101") (name "unconnected-(J14-Pad5)") (class "Default")
      (node (ref "J14") (pin "5") (pinfunction "5_5") (pintype "passive"))
    )
    (net (code "102") (name "unconnected-(J14-Pad6)") (class "Default")
      (node (ref "J14") (pin "6") (pinfunction "6_6") (pintype "passive"))
    )
    (net (code "103") (name "unconnected-(J14-Pad7)") (class "Default")
      (node (ref "J14") (pin "7") (pinfunction "7_7") (pintype "passive"))
    )
    (net (code "104") (name "unconnected-(J14-Pad8)") (class "Default")
      (node (ref "J14") (pin "8") (pinfunction "8_8") (pintype "passive"))
    )
    (net (code "105") (name "unconnected-(J15-Pad1)") (class "Default")
      (node (ref "J15") (pin "1") (pinfunction "1_1") (pintype "passive"))
    )
    (net (code "106") (name "unconnected-(J15-Pad2)") (class "Default")
      (node (ref "J15") (pin "2") (pinfunction "2_2") (pintype "passive"))
    )
    (net (code "107") (name "unconnected-(J15-Pad3)") (class "Default")
      (node (ref "J15") (pin "3") (pinfunction "3_3") (pintype "passive"))
    )
    (net (code "108") (name "unconnected-(J15-Pad4)") (class "Default")
      (node (ref "J15") (pin "4") (pinfunction "4_4") (pintype "passive"))
    )
    (net (code "109") (name "unconnected-(J15-Pad5)") (class "Default")
      (node (ref "J15") (pin "5") (pinfunction "5_5") (pintype "passive"))
    )
    (net (code "110") (name "unconnected-(J15-Pad6)") (class "Default")
      (node (ref "J15") (pin "6") (pinfunction "6_6") (pintype "passive"))
    )
    (net (code "111") (name "unconnected-(J15-Pad7)") (class "Default")
      (node (ref "J15") (pin "7") (pinfunction "7_7") (pintype "passive"))
    )
    (net (code "112") (name "unconnected-(J15-Pad8)") (class "Default")
      (node (ref "J15") (pin "8") (pinfunction "8_8") (pintype "passive"))
    )
    (net (code "113") (name "unconnected-(J16-Pad1)") (class "Default")
      (node (ref "J16") (pin "1") (pinfunction "1_1") (pintype "passive"))
    )
    (net (code "114") (name "unconnected-(J16-Pad2)") (class "Default")
      (node (ref "J16") (pin "2") (pinfunction "2_2") (pintype "passive"))
    )
    (net (code "115") (name "unconnected-(J16-Pad3)") (class "Default")
      (node (ref "J16") (pin "3") (pinfunction "3_3") (pintype "passive"))
    )
    (net (code "116") (name "unconnected-(J16-Pad4)") (class "Default")
      (node (ref "J16") (pin "4") (pinfunction "4_4") (pintype "passive"))
    )
    (net (code "117") (name "unconnected-(J16-Pad5)") (class "Default")
      (node (ref "J16") (pin "5") (pinfunction "5_5") (pintype "passive"))
    )
    (net (code "118") (name "unconnected-(J16-Pad6)") (class "Default")
      (node (ref "J16") (pin "6") (pinfunction "6_6") (pintype "passive"))
    )
    (net (code "119") (name "unconnected-(J16-Pad7)") (class "Default")
      (node (ref "J16") (pin "7") (pinfunction "7_7") (pintype "passive"))
    )
    (net (code "120") (name "unconnected-(J16-Pad8)") (class "Default")
      (node (ref "J16") (pin "8") (pinfunction "8_8") (pintype "passive"))
    )
    (net (code "121") (name "unconnected-(J17-Pad1)") (class "Default")
      (node (ref "J17") (pin "1") (pinfunction "1_1") (pintype "passive"))
    )
    (net (code "122") (name "unconnected-(J17-Pad2)") (class "Default")
      (node (ref "J17") (pin "2") (pinfunction "2_2") (pintype "passive"))
    )
    (net (code "123") (name "unconnected-(J17-Pad3)") (class "Default")
      (node (ref "J17") (pin "3") (pinfunction "3_3") (pintype "passive"))
    )
    (net (code "124") (name "unconnected-(J17-Pad4)") (class "Default")
      (node (ref "J17") (pin "4") (pinfunction "4_4") (pintype "passive"))
    )
    (net (code "125") (name "unconnected-(J17-Pad5)") (class "Default")
      (node (ref "J17") (pin "5") (pinfunction "5_5") (pintype "passive"))
    )
    (net (code "126") (name "unconnected-(J17-Pad6)") (class "Default")
      (node (ref "J17") (pin "6") (pinfunction "6_6") (pintype "passive"))
    )
    (net (code "127") (name "unconnected-(J17-Pad7)") (class "Default")
      (node (ref "J17") (pin "7") (pinfunction "7_7") (pintype "passive"))
    )
    (net (code "128") (name "unconnected-(J17-Pad8)") (class "Default")
      (node (ref "J17") (pin "8") (pinfunction "8_8") (pintype "passive"))
    )
    (net (code "129") (name "unconnected-(J17-Pad9)") (class "Default")
      (node (ref "J17") (pin "9") (pinfunction "9_9") (pintype "passive"))
    )
    (net (code "130") (name "unconnected-(J17-Pad10)") (class "Default")
      (node (ref "J17") (pin "10") (pinfunction "10_10") (pintype "passive"))
    )
    (net (code "131") (name "unconnected-(J17-Pad11)") (class "Default")
      (node (ref "J17") (pin "11") (pinfunction "11_11") (pintype "passive"))
    )
    (net (code "132") (name "unconnected-(J17-Pad12)") (class "Default")
      (node (ref "J17") (pin "12") (pinfunction "12_12") (pintype "passive"))
    )
    (net (code "133") (name "unconnected-(J20-Pad1)") (class "Default")
      (node (ref "J20") (pin "1") (pinfunction "1_1") (pintype "passive"))
    )
    (net (code "134") (name "unconnected-(J20-Pad2)") (class "Default")
      (node (ref "J20") (pin "2") (pinfunction "2_2") (pintype "passive"))
    )
    (net (code "135") (name "unconnected-(J20-Pad3)") (class "Default")
      (node (ref "J20") (pin "3") (pinfunction "3_3") (pintype "passive"))
    )
    (net (code "136") (name "unconnected-(J20-Pad4)") (class "Default")
      (node (ref "J20") (pin "4") (pinfunction "4_4") (pintype "passive"))
    )
    (net (code "137") (name "unconnected-(J21-Pad1)") (class "Default")
      (node (ref "J21") (pin "1") (pinfunction "1_1") (pintype "passive"))
    )
    (net (code "138") (name "unconnected-(J21-Pad2)") (class "Default")
      (node (ref "J21") (pin "2") (pinfunction "2_2") (pintype "passive"))
    )
    (net (code "139") (name "unconnected-(J21-Pad3)") (class "Default")
      (node (ref "J21") (pin "3") (pinfunction "3_3") (pintype "passive"))
    )
    (net (code "140") (name "unconnected-(J21-Pad4)") (class "Default")
      (node (ref "J21") (pin "4") (pinfunction "4_4") (pintype "passive"))
    )
    (net (code "141") (name "unconnected-(J21-Pad5)") (class "Default")
      (node (ref "J21") (pin "5") (pinfunction "5_5") (pintype "passive"))
    )
    (net (code "142") (name "unconnected-(J22-Pad1)") (class "Default")
      (node (ref "J22") (pin "1") (pinfunction "1_1") (pintype "passive"))
    )
    (net (code "143") (name "unconnected-(J22-Pad2)") (class "Default")
      (node (ref "J22") (pin "2") (pinfunction "2_2") (pintype "passive"))
    )
    (net (code "144") (name "unconnected-(J22-Pad3)") (class "Default")
      (node (ref "J22") (pin "3") (pinfunction "3_3") (pintype "passive"))
    )
    (net (code "145") (name "unconnected-(J22-Pad4)") (class "Default")
      (node (ref "J22") (pin "4") (pinfunction "4_4") (pintype "passive"))
    )
    (net (code "146") (name "unconnected-(J22-Pad5)") (class "Default")
      (node (ref "J22") (pin "5") (pinfunction "5_5") (pintype "passive"))
    )
    (net (code "147") (name "unconnected-(J22-Pad6)") (class "Default")
      (node (ref "J22") (pin "6") (pinfunction "6_6") (pintype "passive"))
    )
    (net (code "148") (name "unconnected-(J22-Pad7)") (class "Default")
      (node (ref "J22") (pin "7") (pinfunction "7_7") (pintype "passive"))
    )
    (net (code "149") (name "unconnected-(J22-Pad8)") (class "Default")
      (node (ref "J22") (pin "8") (pinfunction "8_8") (pintype "passive"))
    )
    (net (code "150") (name "unconnected-(J22-Pad9)") (class "Default")
      (node (ref "J22") (pin "9") (pinfunction "9_9") (pintype "passive"))
    )
    (net (code "151") (name "unconnected-(J22-Pad10)") (class "Default")
      (node (ref "J22") (pin "10") (pinfunction "10_10") (pintype "passive"))
    )
    (net (code "152") (name "unconnected-(J22-Pad11)") (class "Default")
      (node (ref "J22") (pin "11") (pinfunction "11_11") (pintype "passive"))
    )
    (net (code "153") (name "unconnected-(J22-Pad12)") (class "Default")
      (node (ref "J22") (pin "12") (pinfunction "12_12") (pintype "passive"))
    )
    (net (code "154") (name "unconnected-(J23-Pad1)") (class "Default")
      (node (ref "J23") (pin "1") (pinfunction "1_1") (pintype "passive"))
    )
    (net (code "155") (name "unconnected-(J23-Pad2)") (class "Default")
      (node (ref "J23") (pin "2") (pinfunction "2_2") (pintype "passive"))
    )
    (net (code "156") (name "unconnected-(J23-Pad3)") (class "Default")
      (node (ref "J23") (pin "3") (pinfunction "3_3") (pintype "passive"))
    )
    (net (code "157") (name "unconnected-(J23-Pad4)") (class "Default")
      (node (ref "J23") (pin "4") (pinfunction "4_4") (pintype "passive"))
    )
    (net (code "158") (name "unconnected-(J23-Pad5)") (class "Default")
      (node (ref "J23") (pin "5") (pinfunction "5_5") (pintype "passive"))
    )
    (net (code "159") (name "unconnected-(J23-Pad6)") (class "Default")
      (node (ref "J23") (pin "6") (pinfunction "6_6") (pintype "passive"))
    )
    (net (code "160") (name "unconnected-(J23-Pad7)") (class "Default")
      (node (ref "J23") (pin "7") (pinfunction "7_7") (pintype "passive"))
    )
    (net (code "161") (name "unconnected-(J23-Pad8)") (class "Default")
      (node (ref "J23") (pin "8") (pinfunction "8_8") (pintype "passive"))
    )
    (net (code "162") (name "unconnected-(J23-Pad9)") (class "Default")
      (node (ref "J23") (pin "9") (pinfunction "9_9") (pintype "passive"))
    )
    (net (code "163") (name "unconnected-(J23-Pad10)") (class "Default")
      (node (ref "J23") (pin "10") (pinfunction "10_10") (pintype "passive"))
    )
    (net (code "164") (name "unconnected-(J23-Pad11)") (class "Default")
      (node (ref "J23") (pin "11") (pinfunction "11_11") (pintype "passive"))
    )
    (net (code "165") (name "unconnected-(J23-Pad12)") (class "Default")
      (node (ref "J23") (pin "12") (pinfunction "12_12") (pintype "passive"))
    )
    (net (code "166") (name "unconnected-(J24-Pad1)") (class "Default")
      (node (ref "J24") (pin "1") (pinfunction "1_1") (pintype "passive"))
    )
    (net (code "167") (name "unconnected-(J24-Pad2)") (class "Default")
      (node (ref "J24") (pin "2") (pinfunction "2_2") (pintype "passive"))
    )
    (net (code "168") (name "unconnected-(J24-Pad3)") (class "Default")
      (node (ref "J24") (pin "3") (pinfunction "3_3") (pintype "passive"))
    )
    (net (code "169") (name "unconnected-(J24-Pad4)") (class "Default")
      (node (ref "J24") (pin "4") (pinfunction "4_4") (pintype "passive"))
    )
    (net (code "170") (name "unconnected-(J25-Pad1)") (class "Default")
      (node (ref "J25") (pin "1") (pinfunction "1_1") (pintype "passive"))
    )
    (net (code "171") (name "unconnected-(J25-Pad2)") (class "Default")
      (node (ref "J25") (pin "2") (pinfunction "2_2") (pintype "passive"))
    )
    (net (code "172") (name "unconnected-(J25-Pad3)") (class "Default")
      (node (ref "J25") (pin "3") (pinfunction "3_3") (pintype "passive"))
    )
    (net (code "173") (name "unconnected-(J25-Pad4)") (class "Default")
      (node (ref "J25") (pin "4") (pinfunction "4_4") (pintype "passive"))
    )
    (net (code "174") (name "unconnected-(J25-Pad5)") (class "Default")
      (node (ref "J25") (pin "5") (pinfunction "5_5") (pintype "passive"))
    )
    (net (code "175") (name "unconnected-(J25-Pad6)") (class "Default")
      (node (ref "J25") (pin "6") (pinfunction "6_6") (pintype "passive"))
    )
    (net (code "176") (name "unconnected-(J25-Pad7)") (class "Default")
      (node (ref "J25") (pin "7") (pinfunction "7_7") (pintype "passive"))
    )
    (net (code "177") (name "unconnected-(J25-Pad8)") (class "Default")
      (node (ref "J25") (pin "8") (pinfunction "8_8") (pintype "passive"))
    )
    (net (code "178") (name "unconnected-(J25-Pad9)") (class "Default")
      (node (ref "J25") (pin "9") (pinfunction "9_9") (pintype "passive"))
    )
    (net (code "179") (name "unconnected-(J25-Pad10)") (class "Default")
      (node (ref "J25") (pin "10") (pinfunction "10_10") (pintype "passive"))
    )
    (net (code "180") (name "unconnected-(J25-Pad11)") (class "Default")
      (node (ref "J25") (pin "11") (pinfunction "11_11") (pintype "passive"))
    )
    (net (code "181") (name "unconnected-(J25-Pad12)") (class "Default")
      (node (ref "J25") (pin "12") (pinfunction "12_12") (pintype "passive"))
    )
    (net (code "182") (name "unconnected-(J26-Pad1)") (class "Default")
      (node (ref "J26") (pin "1") (pinfunction "1_1") (pintype "passive"))
    )
    (net (code "183") (name "unconnected-(J26-Pad2)") (class "Default")
      (node (ref "J26") (pin "2") (pinfunction "2_2") (pintype "passive"))
    )
    (net (code "184") (name "unconnected-(J26-Pad3)") (class "Default")
      (node (ref "J26") (pin "3") (pinfunction "3_3") (pintype "passive"))
    )
    (net (code "185") (name "unconnected-(J26-Pad4)") (class "Default")
      (node (ref "J26") (pin "4") (pinfunction "4_4") (pintype "passive"))
    )
    (net (code "186") (name "unconnected-(J26-Pad5)") (class "Default")
      (node (ref "J26") (pin "5") (pinfunction "5_5") (pintype "passive"))
    )
    (net (code "187") (name "unconnected-(J26-Pad6)") (class "Default")
      (node (ref "J26") (pin "6") (pinfunction "6_6") (pintype "passive"))
    )
    (net (code "188") (name "unconnected-(J26-Pad7)") (class "Default")
      (node (ref "J26") (pin "7") (pinfunction "7_7") (pintype "passive"))
    )
    (net (code "189") (name "unconnected-(J26-Pad8)") (class "Default")
      (node (ref "J26") (pin "8") (pinfunction "8_8") (pintype "passive"))
    )
    (net (code "190") (name "unconnected-(J26-Pad9)") (class "Default")
      (node (ref "J26") (pin "9") (pinfunction "9_9") (pintype "passive"))
    )
    (net (code "191") (name "unconnected-(J26-Pad10)") (class "Default")
      (node (ref "J26") (pin "10") (pinfunction "10_10") (pintype "passive"))
    )
    (net (code "192") (name "unconnected-(J26-Pad11)") (class "Default")
      (node (ref "J26") (pin "11") (pinfunction "11_11") (pintype "passive"))
    )
    (net (code "193") (name "unconnected-(J26-Pad12)") (class "Default")
      (node (ref "J26") (pin "12") (pinfunction "12_12") (pintype "passive"))
    )
    (net (code "194") (name "unconnected-(J27-Pad1)") (class "Default")
      (node (ref "J27") (pin "1") (pinfunction "1_1") (pintype "passive"))
    )
    (net (code "195") (name "unconnected-(J27-Pad2)") (class "Default")
      (node (ref "J27") (pin "2") (pinfunction "2_2") (pintype "passive"))
    )
    (net (code "196") (name "unconnected-(J27-Pad3)") (class "Default")
      (node (ref "J27") (pin "3") (pinfunction "3_3") (pintype "passive"))
    )
    (net (code "197") (name "unconnected-(J27-Pad4)") (class "Default")
      (node (ref "J27") (pin "4") (pinfunction "4_4") (pintype "passive"))
    )
    (net (code "198") (name "unconnected-(J27-Pad5)") (class "Default")
      (node (ref "J27") (pin "5") (pinfunction "5_5") (pintype "passive"))
    )
    (net (code "199") (name "unconnected-(J27-Pad6)") (class "Default")
      (node (ref "J27") (pin "6") (pinfunction "6_6") (pintype "passive"))
    )
    (net (code "200") (name "unconnected-(J27-Pad7)") (class "Default")
      (node (ref "J27") (pin "7") (pinfunction "7_7") (pintype "passive"))
    )
    (net (code "201") (name "unconnected-(J27-Pad8)") (class "Default")
      (node (ref "J27") (pin "8") (pinfunction "8_8") (pintype "passive"))
    )
    (net (code "202") (name "unconnected-(J27-Pad9)") (class "Default")
      (node (ref "J27") (pin "9") (pinfunction "9_9") (pintype "passive"))
    )
    (net (code "203") (name "unconnected-(J27-Pad10)") (class "Default")
      (node (ref "J27") (pin "10") (pinfunction "10_10") (pintype "passive"))
    )
    (net (code "204") (name "unconnected-(J27-Pad11)") (class "Default")
      (node (ref "J27") (pin "11") (pinfunction "11_11") (pintype "passive"))
    )
    (net (code "205") (name "unconnected-(J27-Pad12)") (class "Default")
      (node (ref "J27") (pin "12") (pinfunction "12_12") (pintype "passive"))
    )
    (net (code "206") (name "unconnected-(J28-Pad1)") (class "Default")
      (node (ref "J28") (pin "1") (pinfunction "1_1") (pintype "passive"))
    )
    (net (code "207") (name "unconnected-(J28-Pad2)") (class "Default")
      (node (ref "J28") (pin "2") (pinfunction "2_2") (pintype "passive"))
    )
    (net (code "208") (name "unconnected-(J28-Pad3)") (class "Default")
      (node (ref "J28") (pin "3") (pinfunction "3_3") (pintype "passive"))
    )
    (net (code "209") (name "unconnected-(J28-Pad4)") (class "Default")
      (node (ref "J28") (pin "4") (pinfunction "4_4") (pintype "passive"))
    )
    (net (code "210") (name "unconnected-(J28-Pad5)") (class "Default")
      (node (ref "J28") (pin "5") (pinfunction "5_5") (pintype "passive"))
    )
    (net (code "211") (name "unconnected-(J28-Pad6)") (class "Default")
      (node (ref "J28") (pin "6") (pinfunction "6_6") (pintype "passive"))
    )
    (net (code "212") (name "unconnected-(J28-Pad7)") (class "Default")
      (node (ref "J28") (pin "7") (pinfunction "7_7") (pintype "passive"))
    )
    (net (code "213") (name "unconnected-(J28-Pad8)") (class "Default")
      (node (ref "J28") (pin "8") (pinfunction "8_8") (pintype "passive"))
    )
    (net (code "214") (name "unconnected-(J28-Pad9)") (class "Default")
      (node (ref "J28") (pin "9") (pinfunction "9_9") (pintype "passive"))
    )
    (net (code "215") (name "unconnected-(J28-Pad10)") (class "Default")
      (node (ref "J28") (pin "10") (pinfunction "10_10") (pintype "passive"))
    )
    (net (code "216") (name "unconnected-(J28-Pad11)") (class "Default")
      (node (ref "J28") (pin "11") (pinfunction "11_11") (pintype "passive"))
    )
    (net (code "217") (name "unconnected-(J28-Pad12)") (class "Default")
      (node (ref "J28") (pin "12") (pinfunction "12_12") (pintype "passive"))
    )
    (net (code "218") (name "unconnected-(J43-Pad1)") (class "Default")
      (node (ref "J43") (pin "1") (pinfunction "1_1") (pintype "passive"))
    )
    (net (code "219") (name "unconnected-(J43-Pad2)") (class "Default")
      (node (ref "J43") (pin "2") (pinfunction "2_2") (pintype "passive"))
    )
    (net (code "220") (name "unconnected-(J43-Pad3)") (class "Default")
      (node (ref "J43") (pin "3") (pinfunction "3_3") (pintype "passive"))
    )
    (net (code "221") (name "unconnected-(J43-Pad4)") (class "Default")
      (node (ref "J43") (pin "4") (pinfunction "4_4") (pintype "passive"))
    )
    (net (code "222") (name "unconnected-(J45-Pad1)") (class "Default")
      (node (ref "J45") (pin "1") (pinfunction "1_1") (pintype "passive"))
    )
    (net (code "223") (name "unconnected-(J45-Pad2)") (class "Default")
      (node (ref "J45") (pin "2") (pinfunction "2_2") (pintype "passive"))
    )
    (net (code "224") (name "unconnected-(J45-Pad3)") (class "Default")
      (node (ref "J45") (pin "3") (pinfunction "3_3") (pintype "passive"))
    )
    (net (code "225") (name "unconnected-(J57-Pad1)") (class "Default")
      (node (ref "J57") (pin "1") (pinfunction "1_1") (pintype "passive"))
    )
    (net (code "226") (name "unconnected-(J57-Pad2)") (class "Default")
      (node (ref "J57") (pin "2") (pinfunction "2_2") (pintype "passive"))
    )
    (net (code "227") (name "unconnected-(J57-Pad3)") (class "Default")
      (node (ref "J57") (pin "3") (pinfunction "3_3") (pintype "passive"))
    )
    (net (code "228") (name "unconnected-(J57-Pad4)") (class "Default")
      (node (ref "J57") (pin "4") (pinfunction "4_4") (pintype "passive"))
    )
    (net (code "229") (name "unconnected-(U1-NC-Pad4)") (class "Default")
      (node (ref "U1") (pin "4") (pinfunction "NC_4") (pintype "no_connect"))
    )
  )
)
